# misc.net
KiCad netlist of a schematic drawn in Altium Designer
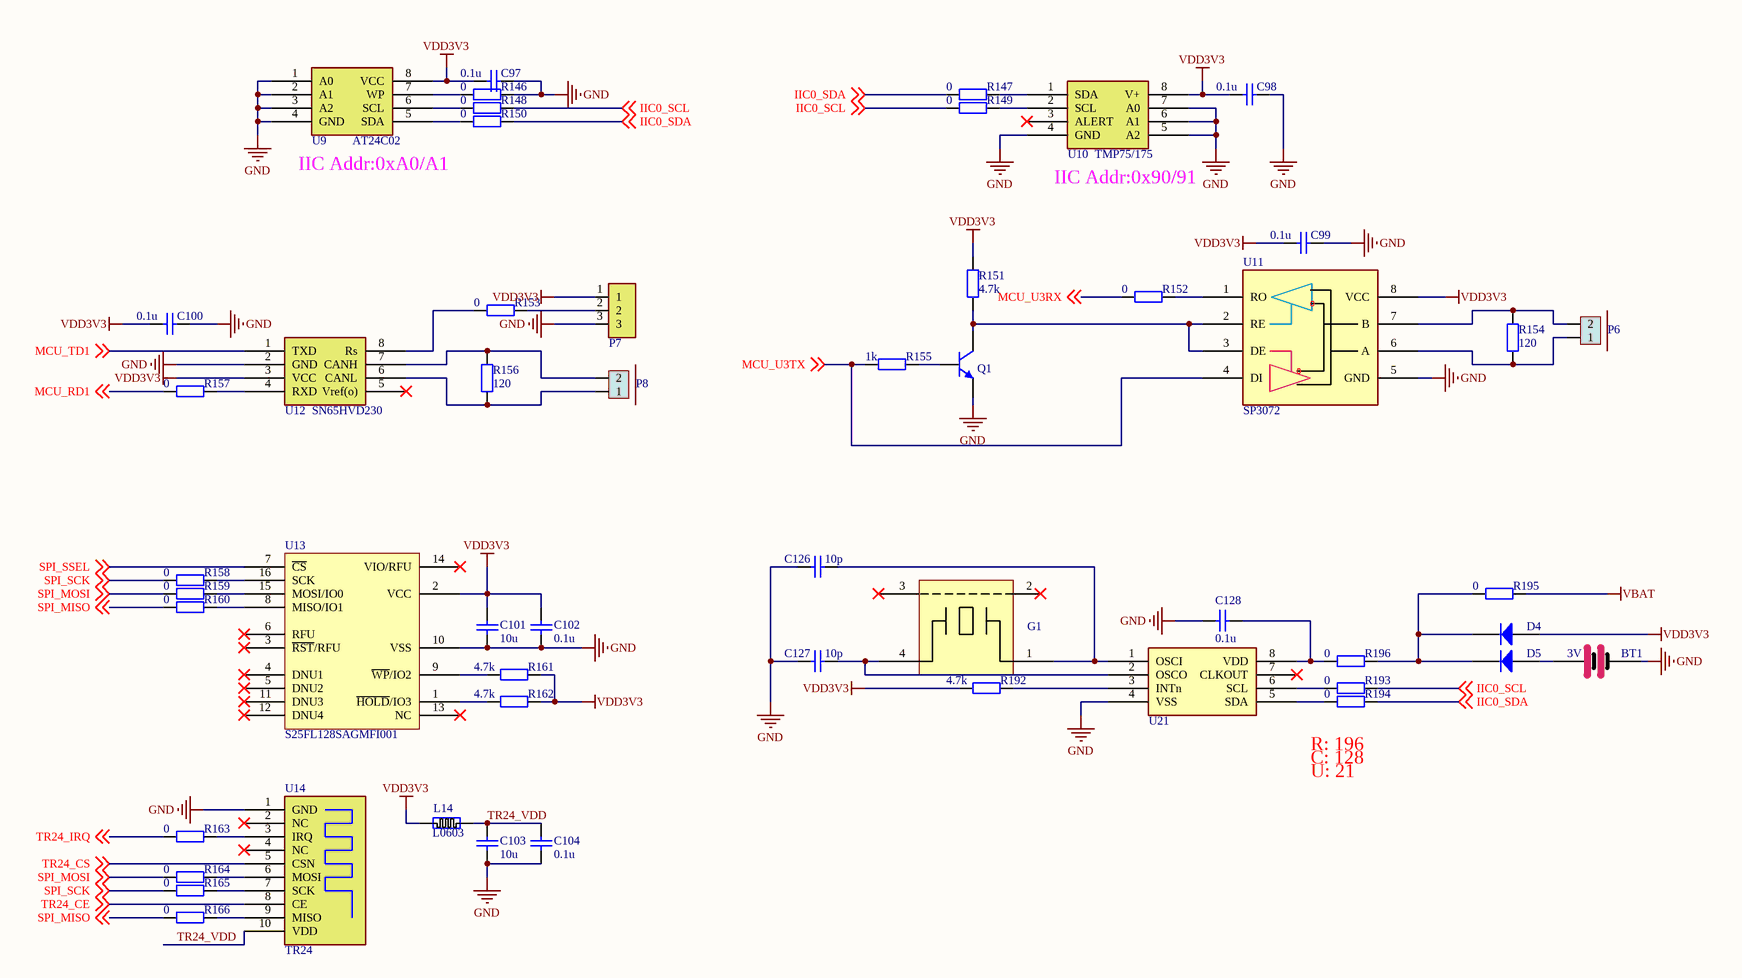
[diagram p0: misc.SchDoc]

(export (version "E")
  (design (tool "Eeschema 10.0.6"))
  (components
    (comp (ref "BT1")
      (value "3V")
      (footprint "BT_SMT")
      (description "贴片电池座")
      (libsource (lib "lpc2368") (part "BT_SMT"))
    )
    (comp (ref "C97")
      (value "0.1u")
      (footprint "C0603")
      (description "0603 Capacitor without Polarity")
      (libsource (lib "lpc2368") (part "CAP0603"))
    )
    (comp (ref "C98")
      (value "0.1u")
      (footprint "C0603")
      (description "0603 Capacitor without Polarity")
      (libsource (lib "lpc2368") (part "CAP0603"))
    )
    (comp (ref "C99")
      (value "0.1u")
      (footprint "C0603")
      (description "0603 Capacitor without Polarity")
      (libsource (lib "lpc2368") (part "CAP0603"))
    )
    (comp (ref "C100")
      (value "0.1u")
      (footprint "C0603")
      (description "0603 Capacitor without Polarity")
      (libsource (lib "lpc2368") (part "CAP0603"))
    )
    (comp (ref "C101")
      (value "10u")
      (footprint "C0603")
      (description "0603 Capacitor without Polarity")
      (libsource (lib "lpc2368") (part "CAP0603"))
    )
    (comp (ref "C102")
      (value "0.1u")
      (footprint "C0603")
      (description "0603 Capacitor without Polarity")
      (libsource (lib "lpc2368") (part "CAP0603"))
    )
    (comp (ref "C103")
      (value "10u")
      (footprint "C0603")
      (description "0603 Capacitor without Polarity")
      (libsource (lib "lpc2368") (part "CAP0603"))
    )
    (comp (ref "C104")
      (value "0.1u")
      (footprint "C0603")
      (description "0603 Capacitor without Polarity")
      (libsource (lib "lpc2368") (part "CAP0603"))
    )
    (comp (ref "C126")
      (value "10p")
      (footprint "C0603")
      (description "0603 Capacitor without Polarity")
      (libsource (lib "lpc2368") (part "CAP0603"))
    )
    (comp (ref "C127")
      (value "10p")
      (footprint "C0603")
      (description "0603 Capacitor without Polarity")
      (libsource (lib "lpc2368") (part "CAP0603"))
    )
    (comp (ref "C128")
      (value "0.1u")
      (footprint "C0603")
      (description "0603 Capacitor without Polarity")
      (libsource (lib "lpc2368") (part "CAP0603"))
    )
    (comp (ref "D4")
      (value "D1N_SMT")
      (footprint "DIODE-SMT")
      (description "贴片二极管")
      (libsource (lib "lpc2368") (part "DIODE_SMT"))
    )
    (comp (ref "D5")
      (value "D1N_SMT")
      (footprint "DIODE-SMT")
      (description "贴片二极管")
      (libsource (lib "lpc2368") (part "DIODE_SMT"))
    )
    (comp (ref "G1")
      (value "Crystal-32768hz")
      (footprint "x4-0408")
      (description "Crystal 32.768k for RTC")
      (libsource (lib "lpc2368") (part "Crystal-32768hz"))
    )
    (comp (ref "L14")
      (value "L0603")
      (footprint "L0603")
      (description "0603 Inductor")
      (libsource (lib "lpc2368") (part "L0603"))
    )
    (comp (ref "P6")
      (value "PIN")
      (footprint "con-i150")
      (description "Connectors with two pins")
      (libsource (lib "lpc2368") (part "SIP2"))
    )
    (comp (ref "P7")
      (value "SIP3")
      (footprint "HDR1X3")
      (description "单排3芯插针/座")
      (libsource (lib "lpc2368") (part "SIP3"))
    )
    (comp (ref "P8")
      (value "PIN")
      (footprint "con-i150")
      (description "Connectors with two pins")
      (libsource (lib "lpc2368") (part "SIP2"))
    )
    (comp (ref "Q1")
      (value "NPN_SOT23")
      (footprint "T-SOT23")
      (description "NPN贴片封装,eg.S8050")
      (libsource (lib "lpc2368") (part "NPN_SOT23"))
    )
    (comp (ref "R146")
      (value "0")
      (footprint "R0603")
      (description "0603 Resistor")
      (libsource (lib "lpc2368") (part "RES0603"))
    )
    (comp (ref "R147")
      (value "0")
      (footprint "R0603")
      (description "0603 Resistor")
      (libsource (lib "lpc2368") (part "RES0603"))
    )
    (comp (ref "R148")
      (value "0")
      (footprint "R0603")
      (description "0603 Resistor")
      (libsource (lib "lpc2368") (part "RES0603"))
    )
    (comp (ref "R149")
      (value "0")
      (footprint "R0603")
      (description "0603 Resistor")
      (libsource (lib "lpc2368") (part "RES0603"))
    )
    (comp (ref "R150")
      (value "0")
      (footprint "R0603")
      (description "0603 Resistor")
      (libsource (lib "lpc2368") (part "RES0603"))
    )
    (comp (ref "R151")
      (value "4.7k")
      (footprint "R0603")
      (description "0603 Resistor")
      (libsource (lib "") (part "RES0603_2"))
    )
    (comp (ref "R152")
      (value "0")
      (footprint "R0603")
      (description "0603 Resistor")
      (libsource (lib "lpc2368") (part "RES0603"))
    )
    (comp (ref "R153")
      (value "0")
      (footprint "R0603")
      (description "0603 Resistor")
      (libsource (lib "lpc2368") (part "RES0603"))
    )
    (comp (ref "R154")
      (value "120")
      (footprint "R0603")
      (description "0603 Resistor")
      (libsource (lib "") (part "RES0603_2"))
    )
    (comp (ref "R155")
      (value "1k")
      (footprint "R0603")
      (description "0603 Resistor")
      (libsource (lib "lpc2368") (part "RES0603"))
    )
    (comp (ref "R156")
      (value "120")
      (footprint "R0603")
      (description "0603 Resistor")
      (libsource (lib "") (part "RES0603_2"))
    )
    (comp (ref "R157")
      (value "0")
      (footprint "R0603")
      (description "0603 Resistor")
      (libsource (lib "lpc2368") (part "RES0603"))
    )
    (comp (ref "R158")
      (value "0")
      (footprint "R0603")
      (description "0603 Resistor")
      (libsource (lib "lpc2368") (part "RES0603"))
    )
    (comp (ref "R159")
      (value "0")
      (footprint "R0603")
      (description "0603 Resistor")
      (libsource (lib "lpc2368") (part "RES0603"))
    )
    (comp (ref "R160")
      (value "0")
      (footprint "R0603")
      (description "0603 Resistor")
      (libsource (lib "lpc2368") (part "RES0603"))
    )
    (comp (ref "R161")
      (value "4.7k")
      (footprint "R0603")
      (description "0603 Resistor")
      (libsource (lib "lpc2368") (part "RES0603"))
    )
    (comp (ref "R162")
      (value "4.7k")
      (footprint "R0603")
      (description "0603 Resistor")
      (libsource (lib "lpc2368") (part "RES0603"))
    )
    (comp (ref "R163")
      (value "0")
      (footprint "R0603")
      (description "0603 Resistor")
      (libsource (lib "lpc2368") (part "RES0603"))
    )
    (comp (ref "R164")
      (value "0")
      (footprint "R0603")
      (description "0603 Resistor")
      (libsource (lib "lpc2368") (part "RES0603"))
    )
    (comp (ref "R165")
      (value "0")
      (footprint "R0603")
      (description "0603 Resistor")
      (libsource (lib "lpc2368") (part "RES0603"))
    )
    (comp (ref "R166")
      (value "0")
      (footprint "R0603")
      (description "0603 Resistor")
      (libsource (lib "lpc2368") (part "RES0603"))
    )
    (comp (ref "R192")
      (value "4.7k")
      (footprint "R0603")
      (description "0603 Resistor")
      (libsource (lib "lpc2368") (part "RES0603"))
    )
    (comp (ref "R193")
      (value "0")
      (footprint "R0603")
      (description "0603 Resistor")
      (libsource (lib "") (part "RES0603_1"))
    )
    (comp (ref "R194")
      (value "0")
      (footprint "R0603")
      (description "0603 Resistor")
      (libsource (lib "") (part "RES0603_1"))
    )
    (comp (ref "R195")
      (value "0")
      (footprint "R0603")
      (description "0603 Resistor")
      (libsource (lib "") (part "RES0603_1"))
    )
    (comp (ref "R196")
      (value "0")
      (footprint "R0603")
      (description "0603 Resistor")
      (libsource (lib "") (part "RES0603_1"))
    )
    (comp (ref "U9")
      (value "AT24C02")
      (footprint "SO8/D/R-PDSO-G8")
      (description "EEPROM")
      (libsource (lib "lpc2368") (part "AT24C02"))
    )
    (comp (ref "U10")
      (value "TMP75/175")
      (footprint "SO8/D/R-PDSO-G8")
      (description "温度传感器")
      (libsource (lib "lpc2368") (part "TMP75/175"))
    )
    (comp (ref "U11")
      (value "SP3072")
      (footprint "SO8/D/R-PDSO-G8")
      (libsource (lib "lpc2368") (part "SP3072EEN-L/TR"))
    )
    (comp (ref "U12")
      (value "SN65HVD230")
      (footprint "SO8/D/R-PDSO-G8")
      (description "CAN PHY")
      (libsource (lib "lpc2368") (part "SN65HVD230"))
    )
    (comp (ref "U13")
      (value "S25FL128SAGMFI001")
      (footprint "SOP16-I50-370")
      (description "SPI FLASH")
      (libsource (lib "lpc2368") (part "S25FL128SAGMFI001"))
    )
    (comp (ref "U14")
      (value "TR24")
      (footprint "TR/JF24")
      (description "2.4G Wireless Reciver & Transmission Module")
      (libsource (lib "lpc2368") (part "TR24"))
    )
    (comp (ref "U21")
      (value "PCF8563")
      (footprint "SOP8-I50-210")
      (description "RTC")
      (libsource (lib "lpc2368") (part "PCF8563"))
    )
  )
  (nets
    (net (code "1") (name "/TR24_VDD") (class "Default")
      (node (ref "C103") (pin "1") (pinfunction "1_1") (pintype "passive"))
      (node (ref "C104") (pin "1") (pinfunction "1_1") (pintype "passive"))
      (node (ref "L14") (pin "2") (pinfunction "2_2") (pintype "passive"))
      (node (ref "U14") (pin "10") (pinfunction "VDD_10") (pintype "passive"))
    )
    (net (code "2") (name "GND") (class "Default")
      (node (ref "BT1") (pin "1") (pintype "passive"))
      (node (ref "C100") (pin "1") (pinfunction "1_1") (pintype "passive"))
      (node (ref "C101") (pin "2") (pinfunction "2_2") (pintype "passive"))
      (node (ref "C102") (pin "2") (pinfunction "2_2") (pintype "passive"))
      (node (ref "C103") (pin "2") (pinfunction "2_2") (pintype "passive"))
      (node (ref "C104") (pin "2") (pinfunction "2_2") (pintype "passive"))
      (node (ref "C126") (pin "1") (pinfunction "1_1") (pintype "passive"))
      (node (ref "C127") (pin "1") (pinfunction "1_1") (pintype "passive"))
      (node (ref "C128") (pin "1") (pinfunction "1_1") (pintype "passive"))
      (node (ref "C97") (pin "1") (pinfunction "1_1") (pintype "passive"))
      (node (ref "C98") (pin "1") (pinfunction "1_1") (pintype "passive"))
      (node (ref "C99") (pin "1") (pinfunction "1_1") (pintype "passive"))
      (node (ref "P7") (pin "3") (pinfunction "3_3") (pintype "passive"))
      (node (ref "Q1") (pin "2") (pinfunction "E_2") (pintype "passive"))
      (node (ref "R146") (pin "2") (pinfunction "2_2") (pintype "passive"))
      (node (ref "U10") (pin "4") (pinfunction "GND_4") (pintype "passive"))
      (node (ref "U10") (pin "5") (pinfunction "A2_5") (pintype "passive"))
      (node (ref "U10") (pin "6") (pinfunction "A1_6") (pintype "passive"))
      (node (ref "U10") (pin "7") (pinfunction "A0_7") (pintype "passive"))
      (node (ref "U11") (pin "5") (pinfunction "GND_5") (pintype "passive"))
      (node (ref "U12") (pin "2") (pinfunction "GND_2") (pintype "passive"))
      (node (ref "U13") (pin "10") (pinfunction "VSS_10") (pintype "passive"))
      (node (ref "U14") (pin "1") (pinfunction "GND_1") (pintype "passive"))
      (node (ref "U21") (pin "4") (pinfunction "VSS_4") (pintype "passive"))
      (node (ref "U9") (pin "1") (pinfunction "A0_1") (pintype "passive"))
      (node (ref "U9") (pin "2") (pinfunction "A1_2") (pintype "passive"))
      (node (ref "U9") (pin "3") (pinfunction "A2_3") (pintype "passive"))
      (node (ref "U9") (pin "4") (pinfunction "GND_4") (pintype "passive"))
    )
    (net (code "3") (name "IIC0_SCL") (class "Default")
      (node (ref "R148") (pin "2") (pinfunction "2_2") (pintype "passive"))
      (node (ref "R149") (pin "1") (pinfunction "1_1") (pintype "passive"))
      (node (ref "R193") (pin "1") (pinfunction "1_1") (pintype "passive"))
    )
    (net (code "4") (name "IIC0_SDA") (class "Default")
      (node (ref "R147") (pin "1") (pinfunction "1_1") (pintype "passive"))
      (node (ref "R150") (pin "2") (pinfunction "2_2") (pintype "passive"))
      (node (ref "R194") (pin "1") (pinfunction "1_1") (pintype "passive"))
    )
    (net (code "5") (name "MCU_RD1") (class "Default")
      (node (ref "R157") (pin "1") (pinfunction "1_1") (pintype "passive"))
    )
    (net (code "6") (name "MCU_TD1") (class "Default")
      (node (ref "U12") (pin "1") (pinfunction "TXD_1") (pintype "passive"))
    )
    (net (code "7") (name "MCU_U3RX") (class "Default")
      (node (ref "R152") (pin "1") (pinfunction "1_1") (pintype "passive"))
    )
    (net (code "8") (name "MCU_U3TX") (class "Default")
      (node (ref "R155") (pin "1") (pinfunction "1_1") (pintype "passive"))
      (node (ref "U11") (pin "4") (pinfunction "DI_4") (pintype "passive"))
    )
    (net (code "9") (name "Net-(BT1-Pad2)") (class "Default")
      (node (ref "BT1") (pin "2") (pintype "passive"))
      (node (ref "D5") (pin "1") (pinfunction "1_1") (pintype "passive"))
    )
    (net (code "10") (name "Net-(D4-Pad2)") (class "Default")
      (node (ref "D4") (pin "2") (pinfunction "2_2") (pintype "passive"))
      (node (ref "D5") (pin "2") (pinfunction "2_2") (pintype "passive"))
      (node (ref "R195") (pin "2") (pinfunction "2_2") (pintype "passive"))
      (node (ref "R196") (pin "1") (pinfunction "1_1") (pintype "passive"))
    )
    (net (code "11") (name "Net-(P7-Pad2)") (class "Default")
      (node (ref "P7") (pin "2") (pinfunction "2_2") (pintype "passive"))
      (node (ref "R153") (pin "2") (pinfunction "2_2") (pintype "passive"))
    )
    (net (code "12") (name "Net-(Q1-B)") (class "Default")
      (node (ref "Q1") (pin "1") (pinfunction "B_1") (pintype "passive"))
      (node (ref "R155") (pin "2") (pinfunction "2_2") (pintype "passive"))
    )
    (net (code "13") (name "Net-(Q1-C)") (class "Default")
      (node (ref "Q1") (pin "3") (pinfunction "C_3") (pintype "passive"))
      (node (ref "R151") (pin "1") (pinfunction "1_1") (pintype "passive"))
      (node (ref "U11") (pin "2") (pinfunction "RE_2") (pintype "passive"))
      (node (ref "U11") (pin "3") (pinfunction "DE_3") (pintype "passive"))
    )
    (net (code "14") (name "Net-(U9-SCL)") (class "Default")
      (node (ref "R148") (pin "1") (pinfunction "1_1") (pintype "passive"))
      (node (ref "U9") (pin "6") (pinfunction "SCL_6") (pintype "passive"))
    )
    (net (code "15") (name "Net-(U9-SDA)") (class "Default")
      (node (ref "R150") (pin "1") (pinfunction "1_1") (pintype "passive"))
      (node (ref "U9") (pin "5") (pinfunction "SDA_5") (pintype "passive"))
    )
    (net (code "16") (name "Net-(U9-WP)") (class "Default")
      (node (ref "R146") (pin "1") (pinfunction "1_1") (pintype "passive"))
      (node (ref "U9") (pin "7") (pinfunction "WP_7") (pintype "passive"))
    )
    (net (code "17") (name "Net-(U10-SCL)") (class "Default")
      (node (ref "R149") (pin "2") (pinfunction "2_2") (pintype "passive"))
      (node (ref "U10") (pin "2") (pinfunction "SCL_2") (pintype "passive"))
    )
    (net (code "18") (name "Net-(U10-SDA)") (class "Default")
      (node (ref "R147") (pin "2") (pinfunction "2_2") (pintype "passive"))
      (node (ref "U10") (pin "1") (pinfunction "SDA_1") (pintype "passive"))
    )
    (net (code "19") (name "Net-(U11-A)") (class "Default")
      (node (ref "P6") (pin "1") (pinfunction "1_1") (pintype "passive"))
      (node (ref "R154") (pin "1") (pinfunction "1_1") (pintype "passive"))
      (node (ref "U11") (pin "6") (pinfunction "A_6") (pintype "passive"))
    )
    (net (code "20") (name "Net-(U11-B)") (class "Default")
      (node (ref "P6") (pin "2") (pinfunction "2_2") (pintype "passive"))
      (node (ref "R154") (pin "2") (pinfunction "2_2") (pintype "passive"))
      (node (ref "U11") (pin "7") (pinfunction "B_7") (pintype "passive"))
    )
    (net (code "21") (name "Net-(U11-RO)") (class "Default")
      (node (ref "R152") (pin "2") (pinfunction "2_2") (pintype "passive"))
      (node (ref "U11") (pin "1") (pinfunction "RO_1") (pintype "passive"))
    )
    (net (code "22") (name "Net-(U12-CANH)") (class "Default")
      (node (ref "P8") (pin "2") (pinfunction "2_2") (pintype "passive"))
      (node (ref "R156") (pin "2") (pinfunction "2_2") (pintype "passive"))
      (node (ref "U12") (pin "7") (pinfunction "CANH_7") (pintype "passive"))
    )
    (net (code "23") (name "Net-(U12-CANL)") (class "Default")
      (node (ref "P8") (pin "1") (pinfunction "1_1") (pintype "passive"))
      (node (ref "R156") (pin "1") (pinfunction "1_1") (pintype "passive"))
      (node (ref "U12") (pin "6") (pinfunction "CANL_6") (pintype "passive"))
    )
    (net (code "24") (name "Net-(U12-RXD)") (class "Default")
      (node (ref "R157") (pin "2") (pinfunction "2_2") (pintype "passive"))
      (node (ref "U12") (pin "4") (pinfunction "RXD_4") (pintype "passive"))
    )
    (net (code "25") (name "Net-(U12-Rs)") (class "Default")
      (node (ref "R153") (pin "1") (pinfunction "1_1") (pintype "passive"))
      (node (ref "U12") (pin "8") (pinfunction "Rs_8") (pintype "passive"))
    )
    (net (code "26") (name "Net-(U13-MISO{slash}IO1)") (class "Default")
      (node (ref "R160") (pin "2") (pinfunction "2_2") (pintype "passive"))
      (node (ref "U13") (pin "8") (pinfunction "MISO/IO1_8") (pintype "passive"))
    )
    (net (code "27") (name "Net-(U13-MOSI{slash}IO0)") (class "Default")
      (node (ref "R159") (pin "2") (pinfunction "2_2") (pintype "passive"))
      (node (ref "U13") (pin "15") (pinfunction "MOSI/IO0_15") (pintype "passive"))
    )
    (net (code "28") (name "Net-(U13-SCK)") (class "Default")
      (node (ref "R158") (pin "2") (pinfunction "2_2") (pintype "passive"))
      (node (ref "U13") (pin "16") (pinfunction "SCK_16") (pintype "passive"))
    )
    (net (code "29") (name "Net-(U13-~{HOLD}{slash}IO3)") (class "Default")
      (node (ref "R162") (pin "1") (pinfunction "1_1") (pintype "passive"))
      (node (ref "U13") (pin "1") (pinfunction "~{HOLD}/IO3_1") (pintype "passive"))
    )
    (net (code "30") (name "Net-(U13-~{WP}{slash}IO2)") (class "Default")
      (node (ref "R161") (pin "1") (pinfunction "1_1") (pintype "passive"))
      (node (ref "U13") (pin "9") (pinfunction "~{WP}/IO2_9") (pintype "passive"))
    )
    (net (code "31") (name "Net-(U14-IRQ)") (class "Default")
      (node (ref "R163") (pin "2") (pinfunction "2_2") (pintype "passive"))
      (node (ref "U14") (pin "3") (pinfunction "IRQ_3") (pintype "passive"))
    )
    (net (code "32") (name "Net-(U14-MISO)") (class "Default")
      (node (ref "R166") (pin "2") (pinfunction "2_2") (pintype "passive"))
      (node (ref "U14") (pin "9") (pinfunction "MISO_9") (pintype "passive"))
    )
    (net (code "33") (name "Net-(U14-MOSI)") (class "Default")
      (node (ref "R164") (pin "2") (pinfunction "2_2") (pintype "passive"))
      (node (ref "U14") (pin "6") (pinfunction "MOSI_6") (pintype "passive"))
    )
    (net (code "34") (name "Net-(U14-SCK)") (class "Default")
      (node (ref "R165") (pin "2") (pinfunction "2_2") (pintype "passive"))
      (node (ref "U14") (pin "7") (pinfunction "SCK_7") (pintype "passive"))
    )
    (net (code "35") (name "Net-(U21-INTn)") (class "Default")
      (node (ref "R192") (pin "2") (pinfunction "2_2") (pintype "passive"))
      (node (ref "U21") (pin "3") (pinfunction "INTn_3") (pintype "passive"))
    )
    (net (code "36") (name "Net-(U21-OSCI)") (class "Default")
      (node (ref "C126") (pin "2") (pinfunction "2_2") (pintype "passive"))
      (node (ref "G1") (pin "1") (pinfunction "1_1") (pintype "passive"))
      (node (ref "U21") (pin "1") (pinfunction "OSCI_1") (pintype "passive"))
    )
    (net (code "37") (name "Net-(U21-OSCO)") (class "Default")
      (node (ref "C127") (pin "2") (pinfunction "2_2") (pintype "passive"))
      (node (ref "G1") (pin "4") (pinfunction "4_4") (pintype "passive"))
      (node (ref "U21") (pin "2") (pinfunction "OSCO_2") (pintype "passive"))
    )
    (net (code "38") (name "Net-(U21-SCL)") (class "Default")
      (node (ref "R193") (pin "2") (pinfunction "2_2") (pintype "passive"))
      (node (ref "U21") (pin "6") (pinfunction "SCL_6") (pintype "passive"))
    )
    (net (code "39") (name "Net-(U21-SDA)") (class "Default")
      (node (ref "R194") (pin "2") (pinfunction "2_2") (pintype "passive"))
      (node (ref "U21") (pin "5") (pinfunction "SDA_5") (pintype "passive"))
    )
    (net (code "40") (name "Net-(U21-VDD)") (class "Default")
      (node (ref "C128") (pin "2") (pinfunction "2_2") (pintype "passive"))
      (node (ref "R196") (pin "2") (pinfunction "2_2") (pintype "passive"))
      (node (ref "U21") (pin "8") (pinfunction "VDD_8") (pintype "passive"))
    )
    (net (code "41") (name "SPI_MISO") (class "Default")
      (node (ref "R160") (pin "1") (pinfunction "1_1") (pintype "passive"))
      (node (ref "R166") (pin "1") (pinfunction "1_1") (pintype "passive"))
    )
    (net (code "42") (name "SPI_MOSI") (class "Default")
      (node (ref "R159") (pin "1") (pinfunction "1_1") (pintype "passive"))
      (node (ref "R164") (pin "1") (pinfunction "1_1") (pintype "passive"))
    )
    (net (code "43") (name "SPI_SCK") (class "Default")
      (node (ref "R158") (pin "1") (pinfunction "1_1") (pintype "passive"))
      (node (ref "R165") (pin "1") (pinfunction "1_1") (pintype "passive"))
    )
    (net (code "44") (name "SPI_SSEL") (class "Default")
      (node (ref "U13") (pin "7") (pinfunction "~{CS}_7") (pintype "passive"))
    )
    (net (code "45") (name "TR24_CE") (class "Default")
      (node (ref "U14") (pin "8") (pinfunction "CE_8") (pintype "passive"))
    )
    (net (code "46") (name "TR24_CS") (class "Default")
      (node (ref "U14") (pin "5") (pinfunction "CSN_5") (pintype "passive"))
    )
    (net (code "47") (name "TR24_IRQ") (class "Default")
      (node (ref "R163") (pin "1") (pinfunction "1_1") (pintype "passive"))
    )
    (net (code "48") (name "VBAT") (class "Default")
      (node (ref "R195") (pin "1") (pinfunction "1_1") (pintype "passive"))
    )
    (net (code "49") (name "VDD3V3") (class "Default")
      (node (ref "C100") (pin "2") (pinfunction "2_2") (pintype "passive"))
      (node (ref "C101") (pin "1") (pinfunction "1_1") (pintype "passive"))
      (node (ref "C102") (pin "1") (pinfunction "1_1") (pintype "passive"))
      (node (ref "C97") (pin "2") (pinfunction "2_2") (pintype "passive"))
      (node (ref "C98") (pin "2") (pinfunction "2_2") (pintype "passive"))
      (node (ref "C99") (pin "2") (pinfunction "2_2") (pintype "passive"))
      (node (ref "D4") (pin "1") (pinfunction "1_1") (pintype "passive"))
      (node (ref "L14") (pin "1") (pinfunction "1_1") (pintype "passive"))
      (node (ref "P7") (pin "1") (pinfunction "1_1") (pintype "passive"))
      (node (ref "R151") (pin "2") (pinfunction "2_2") (pintype "passive"))
      (node (ref "R161") (pin "2") (pinfunction "2_2") (pintype "passive"))
      (node (ref "R162") (pin "2") (pinfunction "2_2") (pintype "passive"))
      (node (ref "R192") (pin "1") (pinfunction "1_1") (pintype "passive"))
      (node (ref "U10") (pin "8") (pinfunction "V+_8") (pintype "passive"))
      (node (ref "U11") (pin "8") (pinfunction "VCC_8") (pintype "passive"))
      (node (ref "U12") (pin "3") (pinfunction "VCC_3") (pintype "passive"))
      (node (ref "U13") (pin "2") (pinfunction "VCC_2") (pintype "passive"))
      (node (ref "U9") (pin "8") (pinfunction "VCC_8") (pintype "passive"))
    )
    (net (code "50") (name "unconnected-(G1-20-Pad3)") (class "Default")
      (node (ref "G1") (pin "3") (pinfunction "20_3") (pintype "passive+no_connect"))
    )
    (net (code "51") (name "unconnected-(G1-Pad2)") (class "Default")
      (node (ref "G1") (pin "2") (pinfunction "2_2") (pintype "passive+no_connect"))
    )
    (net (code "52") (name "unconnected-(U10-ALERT-Pad3)") (class "Default")
      (node (ref "U10") (pin "3") (pinfunction "ALERT_3") (pintype "passive+no_connect"))
    )
    (net (code "53") (name "unconnected-(U12-Vref(o)-Pad5)") (class "Default")
      (node (ref "U12") (pin "5") (pinfunction "Vref(o)_5") (pintype "passive+no_connect"))
    )
    (net (code "54") (name "unconnected-(U13-DNU1-Pad4)") (class "Default")
      (node (ref "U13") (pin "4") (pinfunction "DNU1_4") (pintype "passive+no_connect"))
    )
    (net (code "55") (name "unconnected-(U13-DNU2-Pad5)") (class "Default")
      (node (ref "U13") (pin "5") (pinfunction "DNU2_5") (pintype "passive+no_connect"))
    )
    (net (code "56") (name "unconnected-(U13-DNU3-Pad11)") (class "Default")
      (node (ref "U13") (pin "11") (pinfunction "DNU3_11") (pintype "passive+no_connect"))
    )
    (net (code "57") (name "unconnected-(U13-DNU4-Pad12)") (class "Default")
      (node (ref "U13") (pin "12") (pinfunction "DNU4_12") (pintype "passive+no_connect"))
    )
    (net (code "58") (name "unconnected-(U13-NC-Pad13)") (class "Default")
      (node (ref "U13") (pin "13") (pinfunction "NC_13") (pintype "passive+no_connect"))
    )
    (net (code "59") (name "unconnected-(U13-RFU-Pad6)") (class "Default")
      (node (ref "U13") (pin "6") (pinfunction "RFU_6") (pintype "passive+no_connect"))
    )
    (net (code "60") (name "unconnected-(U13-VIO{slash}RFU-Pad14)") (class "Default")
      (node (ref "U13") (pin "14") (pinfunction "VIO/RFU_14") (pintype "passive+no_connect"))
    )
    (net (code "61") (name "unconnected-(U13-~{RST}{slash}RFU-Pad3)") (class "Default")
      (node (ref "U13") (pin "3") (pinfunction "~{RST}/RFU_3") (pintype "passive+no_connect"))
    )
    (net (code "62") (name "unconnected-(U14-NC-Pad2)") (class "Default")
      (node (ref "U14") (pin "2") (pinfunction "NC_2") (pintype "passive+no_connect"))
    )
    (net (code "63") (name "unconnected-(U14-NC-Pad4)") (class "Default")
      (node (ref "U14") (pin "4") (pinfunction "NC_4") (pintype "passive+no_connect"))
    )
    (net (code "64") (name "unconnected-(U21-CLKOUT-Pad7)") (class "Default")
      (node (ref "U21") (pin "7") (pinfunction "CLKOUT_7") (pintype "passive+no_connect"))
    )
  )
)
